# Microcontroller_Memory.net
KiCad netlist of a schematic drawn in Altium Designer
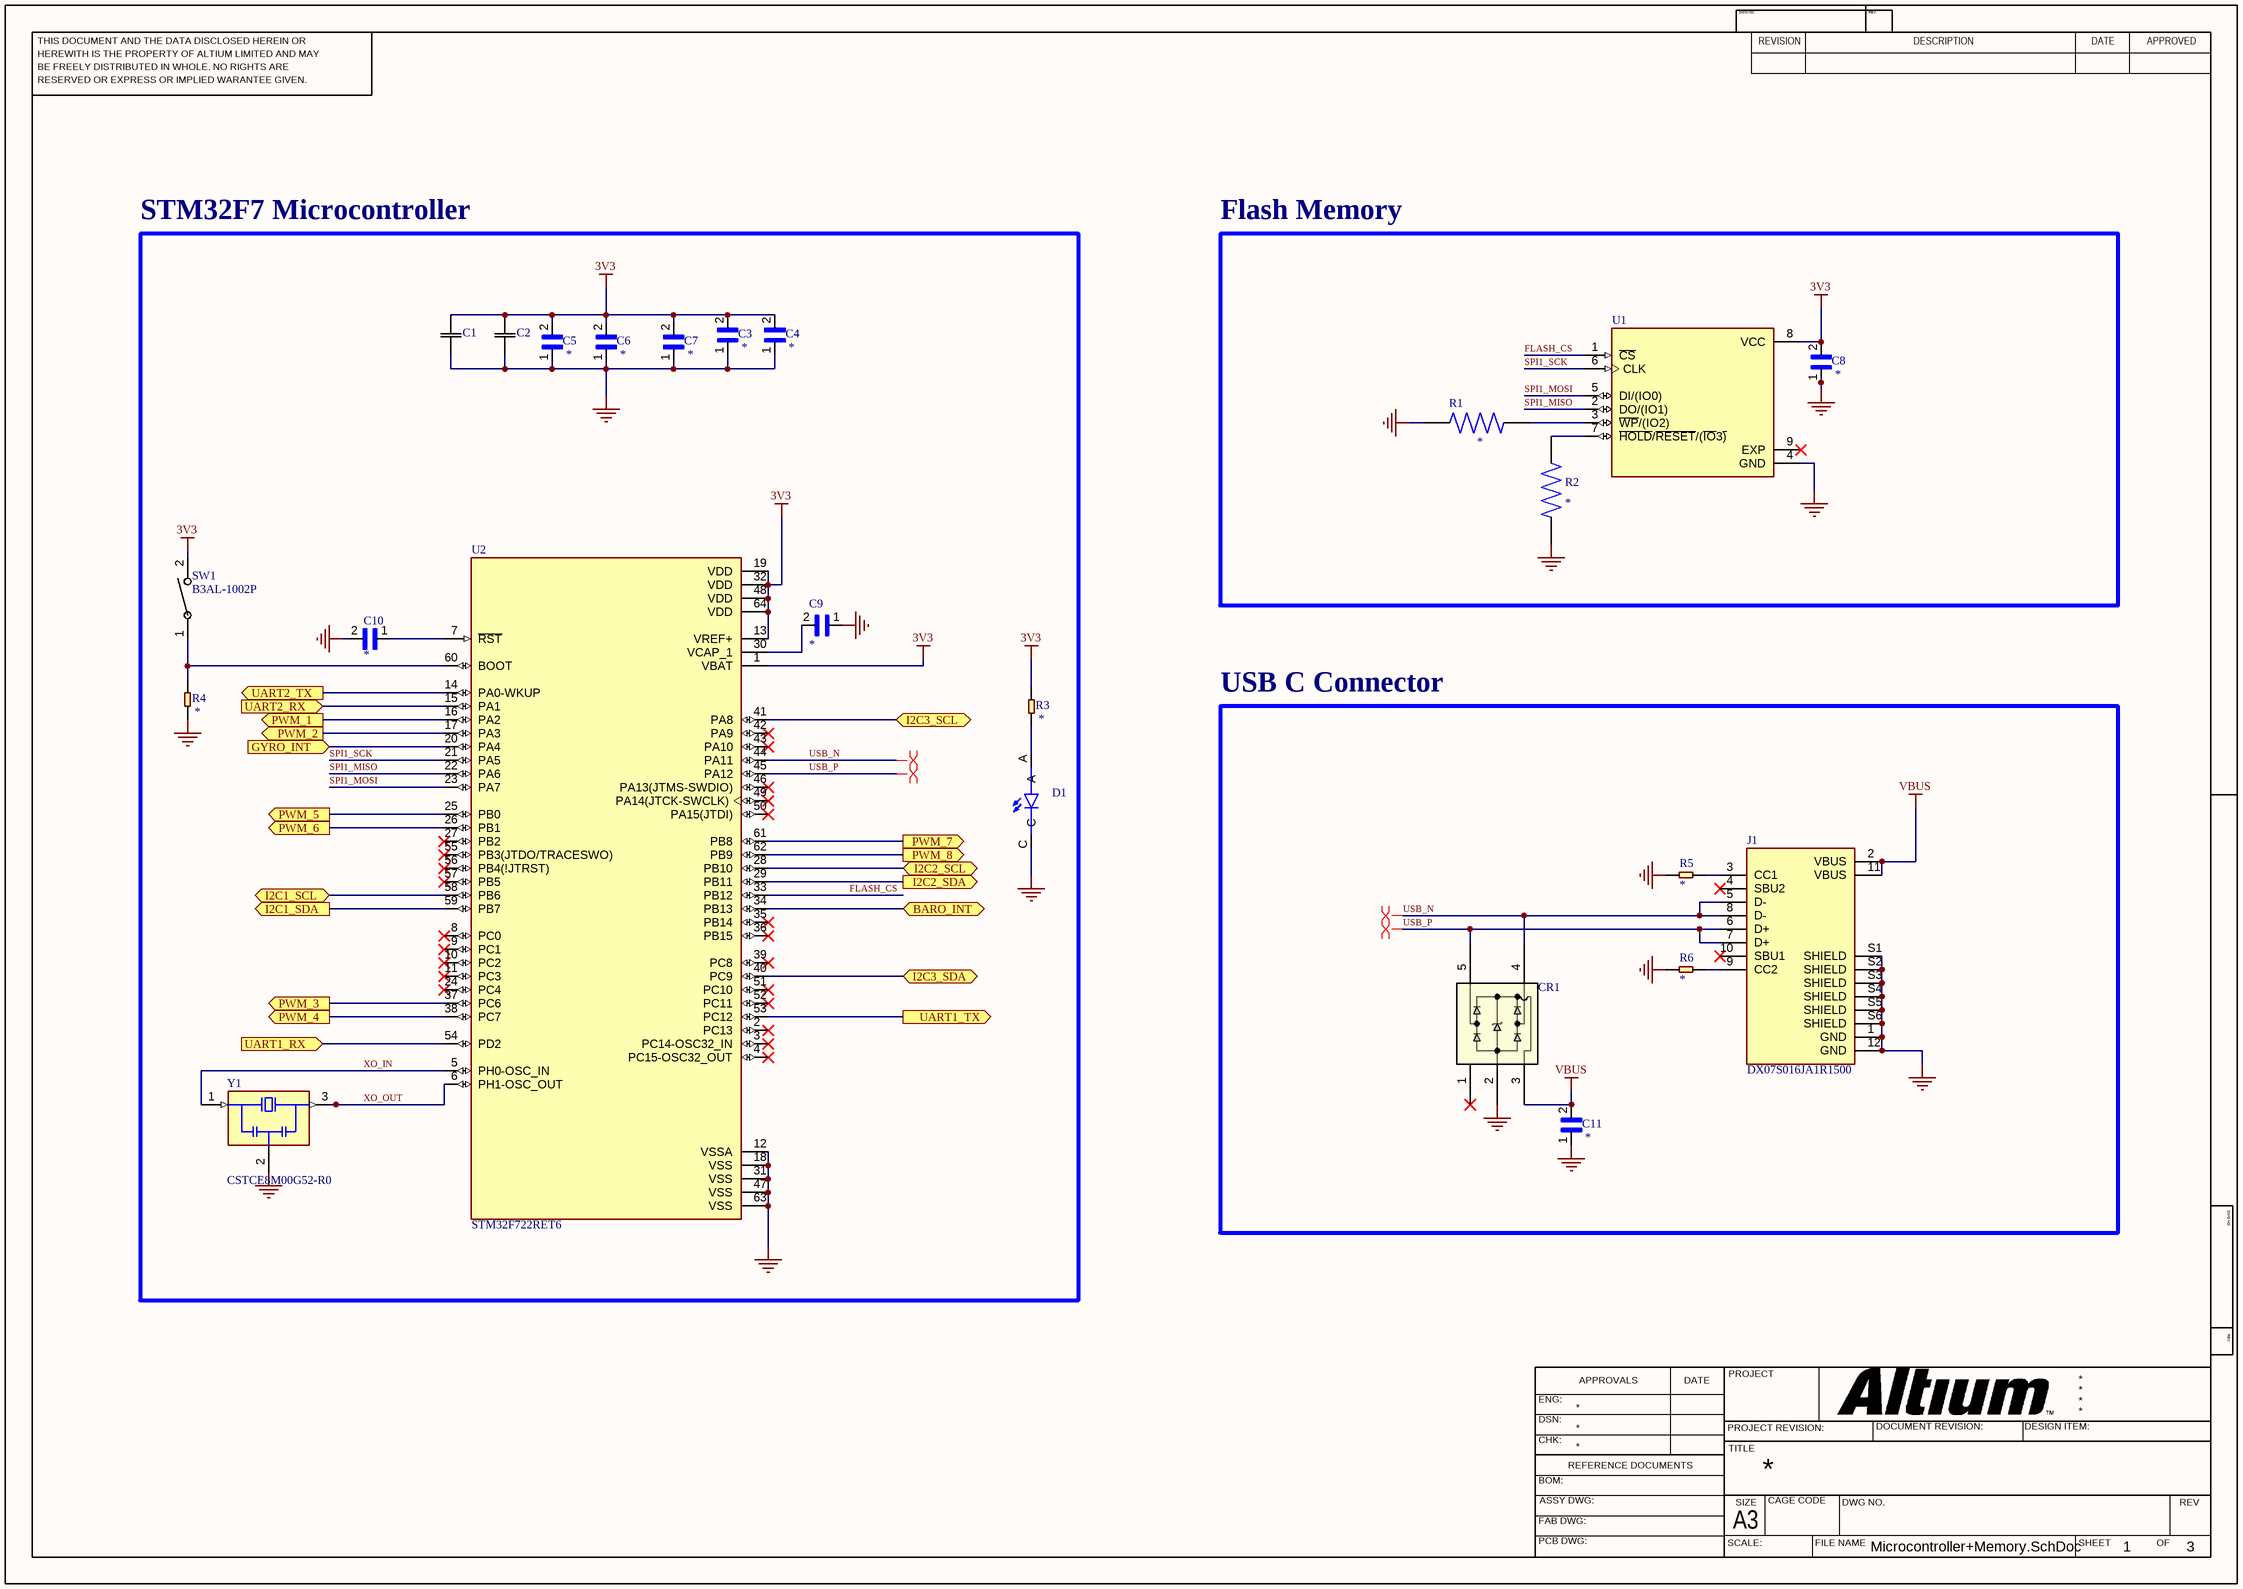
[diagram p0: Microcontroller+Memory.SchDoc]

(export (version "E")
  (design (tool "Eeschema 10.0.6"))
  (components
    (comp (ref "C1")
      (value "CC0402MRX5R6BB106")
      (footprint "CAP_CC0402_YAG")
      (description "No Description Available")
      (libsource (lib "CC0402MRX5R6BB106") (part "CC0402MRX5R6BB106"))
    )
    (comp (ref "C2")
      (value "CC0201MRX5R6BB105")
      (footprint "CAP_CC0201_YAG")
      (description "No Description Available")
      (libsource (lib "CC0201MRX5R6BB105") (part "CC0201MRX5R6BB105"))
    )
    (comp (ref "C3")
      (value "GRM033R61A104KE15D")
      (footprint "CAPC0603X33N")
      (description "SMD capacitor X5R(EIA) with capacitance 0.10uF Tol.10%. Rated voltage 10Vdc 85C")
      (fields (field (name "MF") "Murata Electronics") (field (name "ALTIUM_VALUE") "*"))
      (libsource (lib "GRM033R61A104KE15D") (part "GRM033R61A104KE15D"))
    )
    (comp (ref "C4")
      (value "GRM033R61A104KE15D")
      (footprint "CAPC0603X33N")
      (description "SMD capacitor X5R(EIA) with capacitance 0.10uF Tol.10%. Rated voltage 10Vdc 85C")
      (fields (field (name "MF") "Murata Electronics") (field (name "ALTIUM_VALUE") "*"))
      (libsource (lib "GRM033R61A104KE15D") (part "GRM033R61A104KE15D"))
    )
    (comp (ref "C5")
      (value "GRM033R61A104KE15D")
      (footprint "CAPC0603X33N")
      (description "SMD capacitor X5R(EIA) with capacitance 0.10uF Tol.10%. Rated voltage 10Vdc 85C")
      (fields (field (name "MF") "Murata Electronics") (field (name "ALTIUM_VALUE") "*"))
      (libsource (lib "GRM033R61A104KE15D") (part "GRM033R61A104KE15D"))
    )
    (comp (ref "C6")
      (value "GRM033R61A104KE15D")
      (footprint "CAPC0603X33N")
      (description "SMD capacitor X5R(EIA) with capacitance 0.10uF Tol.10%. Rated voltage 10Vdc 85C")
      (fields (field (name "MF") "Murata Electronics") (field (name "ALTIUM_VALUE") "*"))
      (libsource (lib "GRM033R61A104KE15D") (part "GRM033R61A104KE15D"))
    )
    (comp (ref "C7")
      (value "GRM033R61A104KE15D")
      (footprint "CAPC0603X33N")
      (description "SMD capacitor X5R(EIA) with capacitance 0.10uF Tol.10%. Rated voltage 10Vdc 85C")
      (fields (field (name "MF") "Murata Electronics") (field (name "ALTIUM_VALUE") "*"))
      (libsource (lib "GRM033R61A104KE15D") (part "GRM033R61A104KE15D"))
    )
    (comp (ref "C8")
      (value "GRM033R61A104KE15D")
      (footprint "CAPC0603X33N")
      (description "SMD capacitor X5R(EIA) with capacitance 0.10uF Tol.10%. Rated voltage 10Vdc 85C")
      (fields (field (name "MF") "Murata Electronics") (field (name "ALTIUM_VALUE") "*"))
      (libsource (lib "GRM033R61A104KE15D") (part "GRM033R61A104KE15D"))
    )
    (comp (ref "C9")
      (value "CC0402MRX5R6BB475")
      (footprint "CAPC1005X55N")
      (description "0402 4700000 pF 10 V Â±20 % Tol. X5R Surface Mount Multilayer Ceramic Capacitor")
      (fields (field (name "ALTIUM_VALUE") "*"))
      (libsource (lib "CC0402MRX5R6BB475") (part "CC0402MRX5R6BB475"))
    )
    (comp (ref "C10")
      (value "GRM033R61A104KE15D")
      (footprint "CAPC0603X33N")
      (description "SMD capacitor X5R(EIA) with capacitance 0.10uF Tol.10%. Rated voltage 10Vdc 85C")
      (fields (field (name "MF") "Murata Electronics") (field (name "ALTIUM_VALUE") "*"))
      (libsource (lib "") (part "GRM033R61A104KE15D_1"))
    )
    (comp (ref "C11")
      (value "GRM033R61A104KE15D")
      (footprint "CAPC0603X33N")
      (description "SMD capacitor X5R(EIA) with capacitance 0.10uF Tol.10%. Rated voltage 10Vdc 85C")
      (fields (field (name "MF") "Murata Electronics") (field (name "ALTIUM_VALUE") "*"))
      (libsource (lib "GRM033R61A104KE15D") (part "GRM033R61A104KE15D"))
    )
    (comp (ref "CR1")
      (value "SP3003-02XTG")
      (footprint "SP3003-02XTG:SOT553_LTF")
      (description "No Description Available")
      (libsource (lib "SP3003-02XTG") (part "SP3003-02XTG"))
    )
    (comp (ref "D1")
      (value "LTST-C190KFKT")
      (footprint "LEDM1608X80")
      (description "LED Uni-Color Orange 611nm 2-Pin Chip LED T/R")
      (fields (field (name "MF") "Lite-On Electronics"))
      (libsource (lib "LTST-C190KFKT") (part "LTST-C190KFKT"))
    )
    (comp (ref "J1")
      (value "DX07S016JA1R1500")
      (footprint "JAE_DX07S016JA1R1500")
      (libsource (lib "DX07S016JA1R1500") (part "DX07S016JA1R1500"))
    )
    (comp (ref "R1")
      (value "ERA2AEB512X")
      (footprint "RES_ERA2AEB512X")
      (fields (field (name "ALTIUM_VALUE") "*"))
      (libsource (lib "ERA2AEB512X") (part "ERA2AEB512X"))
    )
    (comp (ref "R2")
      (value "ERA2AEB512X")
      (footprint "RES_ERA2AEB512X")
      (fields (field (name "ALTIUM_VALUE") "*"))
      (libsource (lib "ERA2AEB512X") (part "ERA2AEB512X"))
    )
    (comp (ref "R3")
      (value "SMD-RES-1K-5%-1/16W(0402)")
      (footprint "R0402")
      (description "1 kOhms Â±5% 0.063W, 1/16W Chip Resistor 0402 (1005 Metric) Moisture Resistant Thick Film")
      (fields
        (field (name "ALTIUM_VALUE") "*")
        (field (name "MP") "RC0402JR-071KL")
        (field (name "DIGI-KEY_PART_NUMBER") "311-1.0KJRTR-ND")
      )
      (libsource (lib "") (part "SMD-RES-1K-5%-1/16W(0402)_1"))
    )
    (comp (ref "R4")
      (value "SMD-RES-1K-5%-1/16W(0402)")
      (footprint "R0402")
      (description "1 kOhms Â±5% 0.063W, 1/16W Chip Resistor 0402 (1005 Metric) Moisture Resistant Thick Film")
      (fields
        (field (name "ALTIUM_VALUE") "*")
        (field (name "MP") "RC0402JR-071KL")
        (field (name "DIGI-KEY_PART_NUMBER") "311-1.0KJRTR-ND")
      )
      (libsource (lib "") (part "SMD-RES-1K-5%-1/16W(0402)_1"))
    )
    (comp (ref "R5")
      (value "SMD-RES-1K-5%-1/16W(0402)")
      (footprint "R0402")
      (description "1 kOhms Â±5% 0.063W, 1/16W Chip Resistor 0402 (1005 Metric) Moisture Resistant Thick Film")
      (fields
        (field (name "ALTIUM_VALUE") "*")
        (field (name "MP") "RC0402JR-071KL")
        (field (name "DIGI-KEY_PART_NUMBER") "311-1.0KJRTR-ND")
      )
      (libsource (lib "SMD-RES-1K-5_-1_16W_0402_") (part "SMD-RES-1K-5%-1/16W(0402)"))
    )
    (comp (ref "R6")
      (value "SMD-RES-1K-5%-1/16W(0402)")
      (footprint "R0402")
      (description "1 kOhms Â±5% 0.063W, 1/16W Chip Resistor 0402 (1005 Metric) Moisture Resistant Thick Film")
      (fields
        (field (name "ALTIUM_VALUE") "*")
        (field (name "MP") "RC0402JR-071KL")
        (field (name "DIGI-KEY_PART_NUMBER") "311-1.0KJRTR-ND")
      )
      (libsource (lib "SMD-RES-1K-5_-1_16W_0402_") (part "SMD-RES-1K-5%-1/16W(0402)"))
    )
    (comp (ref "SW1")
      (value "B3AL-1002P")
      (footprint "B3AL-1002P:SW_3AL-1002P_OMR")
      (description "No Description Available")
      (libsource (lib "B3AL-1002P") (part "B3AL-1002P"))
    )
    (comp (ref "U1")
      (value "W25Q256JVEIQ_TR")
      (footprint "SON127P600X800X80-9N")
      (description "FLASH - NOR Memory IC 256Mb (32M x 8) SPI - Quad I/O 133 MHz 8-WSON (8x6)")
      (fields (field (name "MP") "W25Q256JVEIQ TR") (field (name "MF") "Winbond"))
      (libsource (lib "W25Q256JVEIQ_TR") (part "W25Q256JVEIQ_TR"))
    )
    (comp (ref "U2")
      (value "STM32F722RET6")
      (footprint "QFP50P1200X1200X160-64N")
      (description "ARMÂ® CortexÂ®-M7 STM32F7 Microcontroller IC 32-Bit 216MHz 512KB _512K x 8_ FLASH 64-LQFP _10x10_")
      (fields (field (name "MF") "STMicroelectronics"))
      (libsource (lib "STM32F722RET6") (part "STM32F722RET6"))
    )
    (comp (ref "Y1")
      (value "CSTCE8M00G52-R0")
      (footprint "OSC_CSTCE8M00G52-R0")
      (description "8MHz Ceramic Resonator Built in Capacitor 10pF Â±0.2% -20Â°C ~ 80Â°C Surface Mount")
      (fields (field (name "MF") "Murata"))
      (libsource (lib "CSTCE8M00G52-R0") (part "CSTCE8M00G52-R0"))
    )
  )
  (nets
    (net (code "1") (name "/BARO_INT") (class "Default")
      (node (ref "U2") (pin "34") (pinfunction "PB13_34") (pintype "bidirectional"))
    )
    (net (code "2") (name "/FLASH_CS") (class "Default")
      (node (ref "U1") (pin "1") (pinfunction "~{CS}_1") (pintype "input"))
      (node (ref "U2") (pin "33") (pinfunction "PB12_33") (pintype "bidirectional"))
    )
    (net (code "3") (name "/GYRO_INT") (class "Default")
      (node (ref "U2") (pin "20") (pinfunction "PA4_20") (pintype "bidirectional"))
    )
    (net (code "4") (name "/I2C1_SCL") (class "Default")
      (node (ref "U2") (pin "58") (pinfunction "PB6_58") (pintype "bidirectional"))
    )
    (net (code "5") (name "/I2C1_SDA") (class "Default")
      (node (ref "U2") (pin "59") (pinfunction "PB7_59") (pintype "bidirectional"))
    )
    (net (code "6") (name "/I2C2_SCL") (class "Default")
      (node (ref "U2") (pin "28") (pinfunction "PB10_28") (pintype "bidirectional"))
    )
    (net (code "7") (name "/I2C2_SDA") (class "Default")
      (node (ref "U2") (pin "29") (pinfunction "PB11_29") (pintype "bidirectional"))
    )
    (net (code "8") (name "/I2C3_SCL") (class "Default")
      (node (ref "U2") (pin "41") (pinfunction "PA8_41") (pintype "bidirectional"))
    )
    (net (code "9") (name "/I2C3_SDA") (class "Default")
      (node (ref "U2") (pin "40") (pinfunction "PC9_40") (pintype "bidirectional"))
    )
    (net (code "10") (name "/PWM_1") (class "Default")
      (node (ref "U2") (pin "16") (pinfunction "PA2_16") (pintype "bidirectional"))
    )
    (net (code "11") (name "/PWM_2") (class "Default")
      (node (ref "U2") (pin "17") (pinfunction "PA3_17") (pintype "bidirectional"))
    )
    (net (code "12") (name "/PWM_3") (class "Default")
      (node (ref "U2") (pin "37") (pinfunction "PC6_37") (pintype "bidirectional"))
    )
    (net (code "13") (name "/PWM_4") (class "Default")
      (node (ref "U2") (pin "38") (pinfunction "PC7_38") (pintype "bidirectional"))
    )
    (net (code "14") (name "/PWM_5") (class "Default")
      (node (ref "U2") (pin "25") (pinfunction "PB0_25") (pintype "bidirectional"))
    )
    (net (code "15") (name "/PWM_6") (class "Default")
      (node (ref "U2") (pin "26") (pinfunction "PB1_26") (pintype "bidirectional"))
    )
    (net (code "16") (name "/PWM_7") (class "Default")
      (node (ref "U2") (pin "61") (pinfunction "PB8_61") (pintype "bidirectional"))
    )
    (net (code "17") (name "/PWM_8") (class "Default")
      (node (ref "U2") (pin "62") (pinfunction "PB9_62") (pintype "bidirectional"))
    )
    (net (code "18") (name "/SPI1_MISO") (class "Default")
      (node (ref "U1") (pin "2") (pinfunction "DO/(IO1)_2") (pintype "bidirectional"))
      (node (ref "U2") (pin "22") (pinfunction "PA6_22") (pintype "bidirectional"))
    )
    (net (code "19") (name "/SPI1_MOSI") (class "Default")
      (node (ref "U1") (pin "5") (pinfunction "DI/(IO0)_5") (pintype "bidirectional"))
      (node (ref "U2") (pin "23") (pinfunction "PA7_23") (pintype "bidirectional"))
    )
    (net (code "20") (name "/SPI1_SCK") (class "Default")
      (node (ref "U1") (pin "6") (pinfunction "CLK_6") (pintype "input"))
      (node (ref "U2") (pin "21") (pinfunction "PA5_21") (pintype "bidirectional"))
    )
    (net (code "21") (name "/UART1_RX") (class "Default")
      (node (ref "U2") (pin "54") (pinfunction "PD2_54") (pintype "bidirectional"))
    )
    (net (code "22") (name "/UART1_TX") (class "Default")
      (node (ref "U2") (pin "53") (pinfunction "PC12_53") (pintype "bidirectional"))
    )
    (net (code "23") (name "/UART2_RX") (class "Default")
      (node (ref "U2") (pin "15") (pinfunction "PA1_15") (pintype "bidirectional"))
    )
    (net (code "24") (name "/UART2_TX") (class "Default")
      (node (ref "U2") (pin "14") (pinfunction "PA0-WKUP_14") (pintype "bidirectional"))
    )
    (net (code "25") (name "/USB_N") (class "Default")
      (node (ref "CR1") (pin "4") (pinfunction "4_4") (pintype "passive"))
      (node (ref "J1") (pin "5") (pinfunction "D-_5") (pintype "passive"))
      (node (ref "J1") (pin "8") (pinfunction "D-_8") (pintype "passive"))
      (node (ref "U2") (pin "44") (pinfunction "PA11_44") (pintype "bidirectional"))
    )
    (net (code "26") (name "/USB_P") (class "Default")
      (node (ref "CR1") (pin "5") (pinfunction "5_5") (pintype "passive"))
      (node (ref "J1") (pin "6") (pinfunction "D+_6") (pintype "passive"))
      (node (ref "J1") (pin "7") (pinfunction "D+_7") (pintype "passive"))
      (node (ref "U2") (pin "45") (pinfunction "PA12_45") (pintype "bidirectional"))
    )
    (net (code "27") (name "/XO_IN") (class "Default")
      (node (ref "U2") (pin "5") (pinfunction "PH0-OSC_IN_5") (pintype "bidirectional"))
      (node (ref "Y1") (pin "1") (pinfunction "IN_1") (pintype "input"))
    )
    (net (code "28") (name "/XO_OUT") (class "Default")
      (node (ref "U2") (pin "6") (pinfunction "PH1-OSC_OUT_6") (pintype "bidirectional"))
      (node (ref "Y1") (pin "3") (pinfunction "OUT_3") (pintype "output"))
    )
    (net (code "29") (name "3V3") (class "Default")
      (node (ref "C1") (pin "2") (pinfunction "2_2") (pintype "passive"))
      (node (ref "C2") (pin "2") (pinfunction "2_2") (pintype "passive"))
      (node (ref "C3") (pin "2") (pinfunction "2_2") (pintype "passive"))
      (node (ref "C4") (pin "2") (pinfunction "2_2") (pintype "passive"))
      (node (ref "C5") (pin "2") (pinfunction "2_2") (pintype "passive"))
      (node (ref "C6") (pin "2") (pinfunction "2_2") (pintype "passive"))
      (node (ref "C7") (pin "2") (pinfunction "2_2") (pintype "passive"))
      (node (ref "C8") (pin "2") (pinfunction "2_2") (pintype "passive"))
      (node (ref "R3") (pin "2") (pinfunction "2_2") (pintype "passive"))
      (node (ref "SW1") (pin "2") (pinfunction "2_2") (pintype "passive"))
      (node (ref "U1") (pin "8") (pinfunction "VCC_8") (pintype "power_in"))
      (node (ref "U2") (pin "1") (pinfunction "VBAT_1") (pintype "power_in"))
      (node (ref "U2") (pin "13") (pinfunction "VREF+_13") (pintype "power_in"))
      (node (ref "U2") (pin "19") (pinfunction "VDD_19") (pintype "power_in"))
      (node (ref "U2") (pin "32") (pinfunction "VDD_32") (pintype "power_in"))
      (node (ref "U2") (pin "48") (pinfunction "VDD_48") (pintype "power_in"))
      (node (ref "U2") (pin "64") (pinfunction "VDD_64") (pintype "power_in"))
    )
    (net (code "30") (name "GND") (class "Default")
      (node (ref "C1") (pin "1") (pinfunction "1_1") (pintype "passive"))
      (node (ref "C10") (pin "2") (pinfunction "2_2") (pintype "passive"))
      (node (ref "C11") (pin "1") (pinfunction "1_1") (pintype "passive"))
      (node (ref "C2") (pin "1") (pinfunction "1_1") (pintype "passive"))
      (node (ref "C3") (pin "1") (pinfunction "1_1") (pintype "passive"))
      (node (ref "C4") (pin "1") (pinfunction "1_1") (pintype "passive"))
      (node (ref "C5") (pin "1") (pinfunction "1_1") (pintype "passive"))
      (node (ref "C6") (pin "1") (pinfunction "1_1") (pintype "passive"))
      (node (ref "C7") (pin "1") (pinfunction "1_1") (pintype "passive"))
      (node (ref "C8") (pin "1") (pinfunction "1_1") (pintype "passive"))
      (node (ref "C9") (pin "1") (pinfunction "1_1") (pintype "passive"))
      (node (ref "CR1") (pin "2") (pinfunction "2_2") (pintype "passive"))
      (node (ref "D1") (pin "C") (pinfunction "C_C") (pintype "passive"))
      (node (ref "J1") (pin "1") (pinfunction "GND_1") (pintype "power_in"))
      (node (ref "J1") (pin "12") (pinfunction "GND_12") (pintype "power_in"))
      (node (ref "J1") (pin "S1") (pinfunction "SHIELD_S1") (pintype "passive"))
      (node (ref "J1") (pin "S2") (pinfunction "SHIELD_S2") (pintype "passive"))
      (node (ref "J1") (pin "S3") (pinfunction "SHIELD_S3") (pintype "passive"))
      (node (ref "J1") (pin "S4") (pinfunction "SHIELD_S4") (pintype "passive"))
      (node (ref "J1") (pin "S5") (pinfunction "SHIELD_S5") (pintype "passive"))
      (node (ref "J1") (pin "S6") (pinfunction "SHIELD_S6") (pintype "passive"))
      (node (ref "R1") (pin "1") (pinfunction "1_1") (pintype "passive"))
      (node (ref "R2") (pin "1") (pinfunction "1_1") (pintype "passive"))
      (node (ref "R4") (pin "1") (pinfunction "1_1") (pintype "passive"))
      (node (ref "R5") (pin "2") (pinfunction "2_2") (pintype "passive"))
      (node (ref "R6") (pin "2") (pinfunction "2_2") (pintype "passive"))
      (node (ref "U1") (pin "4") (pinfunction "GND_4") (pintype "power_in"))
      (node (ref "U2") (pin "12") (pinfunction "VSSA_12") (pintype "power_in"))
      (node (ref "U2") (pin "18") (pinfunction "VSS_18") (pintype "power_in"))
      (node (ref "U2") (pin "31") (pinfunction "VSS_31") (pintype "power_in"))
      (node (ref "U2") (pin "47") (pinfunction "VSS_47") (pintype "power_in"))
      (node (ref "U2") (pin "63") (pinfunction "VSS_63") (pintype "power_in"))
      (node (ref "Y1") (pin "2") (pinfunction "GND_2") (pintype "power_in"))
    )
    (net (code "31") (name "Net-(D1-PadA)") (class "Default")
      (node (ref "D1") (pin "A") (pinfunction "A_A") (pintype "passive"))
      (node (ref "R3") (pin "1") (pinfunction "1_1") (pintype "passive"))
    )
    (net (code "32") (name "Net-(J1-CC1)") (class "Default")
      (node (ref "J1") (pin "3") (pinfunction "CC1_3") (pintype "passive"))
      (node (ref "R5") (pin "1") (pinfunction "1_1") (pintype "passive"))
    )
    (net (code "33") (name "Net-(J1-CC2)") (class "Default")
      (node (ref "J1") (pin "9") (pinfunction "CC2_9") (pintype "passive"))
      (node (ref "R6") (pin "1") (pinfunction "1_1") (pintype "passive"))
    )
    (net (code "34") (name "Net-(U1-~{HOLD}{slash}~{RESET}{slash}(~{IO}3~{)})") (class "Default")
      (node (ref "R2") (pin "2") (pinfunction "2_2") (pintype "passive"))
      (node (ref "U1") (pin "7") (pinfunction "~{HOLD}/~{RESET}/(~{IO}3~{)}_7") (pintype "bidirectional"))
    )
    (net (code "35") (name "Net-(U1-~{WP}{slash}(IO2))") (class "Default")
      (node (ref "R1") (pin "2") (pinfunction "2_2") (pintype "passive"))
      (node (ref "U1") (pin "3") (pinfunction "~{WP}/(IO2)_3") (pintype "bidirectional"))
    )
    (net (code "36") (name "Net-(U2-BOOT)") (class "Default")
      (node (ref "R4") (pin "2") (pinfunction "2_2") (pintype "passive"))
      (node (ref "SW1") (pin "1") (pinfunction "1_1") (pintype "passive"))
      (node (ref "U2") (pin "60") (pinfunction "BOOT_60") (pintype "bidirectional"))
    )
    (net (code "37") (name "Net-(U2-VCAP_1)") (class "Default")
      (node (ref "C9") (pin "2") (pinfunction "2_2") (pintype "passive"))
      (node (ref "U2") (pin "30") (pinfunction "VCAP_1_30") (pintype "power_in"))
    )
    (net (code "38") (name "Net-(U2-~{RST})") (class "Default")
      (node (ref "C10") (pin "1") (pinfunction "1_1") (pintype "passive"))
      (node (ref "U2") (pin "7") (pinfunction "~{RST}_7") (pintype "input"))
    )
    (net (code "39") (name "VBUS") (class "Default")
      (node (ref "C11") (pin "2") (pinfunction "2_2") (pintype "passive"))
      (node (ref "CR1") (pin "3") (pinfunction "3_3") (pintype "passive"))
      (node (ref "J1") (pin "11") (pinfunction "VBUS_11") (pintype "power_in"))
      (node (ref "J1") (pin "2") (pinfunction "VBUS_2") (pintype "power_in"))
    )
    (net (code "40") (name "unconnected-(CR1-Pad1)") (class "Default")
      (node (ref "CR1") (pin "1") (pinfunction "1_1") (pintype "passive+no_connect"))
    )
    (net (code "41") (name "unconnected-(J1-SBU1-Pad10)") (class "Default")
      (node (ref "J1") (pin "10") (pinfunction "SBU1_10") (pintype "passive+no_connect"))
    )
    (net (code "42") (name "unconnected-(J1-SBU2-Pad4)") (class "Default")
      (node (ref "J1") (pin "4") (pinfunction "SBU2_4") (pintype "passive+no_connect"))
    )
    (net (code "43") (name "unconnected-(U1-EXP-Pad9)") (class "Default")
      (node (ref "U1") (pin "9") (pinfunction "EXP_9") (pintype "passive+no_connect"))
    )
    (net (code "44") (name "unconnected-(U2-PA9-Pad42)") (class "Default")
      (node (ref "U2") (pin "42") (pinfunction "PA9_42") (pintype "bidirectional+no_connect"))
    )
    (net (code "45") (name "unconnected-(U2-PA10-Pad43)") (class "Default")
      (node (ref "U2") (pin "43") (pinfunction "PA10_43") (pintype "bidirectional+no_connect"))
    )
    (net (code "46") (name "unconnected-(U2-PA13(JTMS-SWDIO)-Pad46)") (class "Default")
      (node (ref "U2") (pin "46") (pinfunction "PA13(JTMS-SWDIO)_46") (pintype "bidirectional+no_connect"))
    )
    (net (code "47") (name "unconnected-(U2-PA14(JTCK-SWCLK)-Pad49)") (class "Default")
      (node (ref "U2") (pin "49") (pinfunction "PA14(JTCK-SWCLK)_49") (pintype "bidirectional+no_connect"))
    )
    (net (code "48") (name "unconnected-(U2-PA15(JTDI)-Pad50)") (class "Default")
      (node (ref "U2") (pin "50") (pinfunction "PA15(JTDI)_50") (pintype "bidirectional+no_connect"))
    )
    (net (code "49") (name "unconnected-(U2-PB2-Pad27)") (class "Default")
      (node (ref "U2") (pin "27") (pinfunction "PB2_27") (pintype "bidirectional+no_connect"))
    )
    (net (code "50") (name "unconnected-(U2-PB3(JTDO{slash}TRACESWO)-Pad55)") (class "Default")
      (node (ref "U2") (pin "55") (pinfunction "PB3(JTDO/TRACESWO)_55") (pintype "bidirectional+no_connect"))
    )
    (net (code "51") (name "unconnected-(U2-PB4(!JTRST)-Pad56)") (class "Default")
      (node (ref "U2") (pin "56") (pinfunction "PB4(!JTRST)_56") (pintype "bidirectional+no_connect"))
    )
    (net (code "52") (name "unconnected-(U2-PB5-Pad57)") (class "Default")
      (node (ref "U2") (pin "57") (pinfunction "PB5_57") (pintype "bidirectional+no_connect"))
    )
    (net (code "53") (name "unconnected-(U2-PB14-Pad35)") (class "Default")
      (node (ref "U2") (pin "35") (pinfunction "PB14_35") (pintype "bidirectional+no_connect"))
    )
    (net (code "54") (name "unconnected-(U2-PB15-Pad36)") (class "Default")
      (node (ref "U2") (pin "36") (pinfunction "PB15_36") (pintype "bidirectional+no_connect"))
    )
    (net (code "55") (name "unconnected-(U2-PC0-Pad8)") (class "Default")
      (node (ref "U2") (pin "8") (pinfunction "PC0_8") (pintype "bidirectional+no_connect"))
    )
    (net (code "56") (name "unconnected-(U2-PC1-Pad9)") (class "Default")
      (node (ref "U2") (pin "9") (pinfunction "PC1_9") (pintype "bidirectional+no_connect"))
    )
    (net (code "57") (name "unconnected-(U2-PC2-Pad10)") (class "Default")
      (node (ref "U2") (pin "10") (pinfunction "PC2_10") (pintype "bidirectional+no_connect"))
    )
    (net (code "58") (name "unconnected-(U2-PC3-Pad11)") (class "Default")
      (node (ref "U2") (pin "11") (pinfunction "PC3_11") (pintype "bidirectional+no_connect"))
    )
    (net (code "59") (name "unconnected-(U2-PC4-Pad24)") (class "Default")
      (node (ref "U2") (pin "24") (pinfunction "PC4_24") (pintype "bidirectional+no_connect"))
    )
    (net (code "60") (name "unconnected-(U2-PC8-Pad39)") (class "Default")
      (node (ref "U2") (pin "39") (pinfunction "PC8_39") (pintype "bidirectional+no_connect"))
    )
    (net (code "61") (name "unconnected-(U2-PC10-Pad51)") (class "Default")
      (node (ref "U2") (pin "51") (pinfunction "PC10_51") (pintype "bidirectional+no_connect"))
    )
    (net (code "62") (name "unconnected-(U2-PC11-Pad52)") (class "Default")
      (node (ref "U2") (pin "52") (pinfunction "PC11_52") (pintype "bidirectional+no_connect"))
    )
    (net (code "63") (name "unconnected-(U2-PC13-Pad2)") (class "Default")
      (node (ref "U2") (pin "2") (pinfunction "PC13_2") (pintype "bidirectional+no_connect"))
    )
    (net (code "64") (name "unconnected-(U2-PC14-OSC32_IN-Pad3)") (class "Default")
      (node (ref "U2") (pin "3") (pinfunction "PC14-OSC32_IN_3") (pintype "bidirectional+no_connect"))
    )
    (net (code "65") (name "unconnected-(U2-PC15-OSC32_OUT-Pad4)") (class "Default")
      (node (ref "U2") (pin "4") (pinfunction "PC15-OSC32_OUT_4") (pintype "bidirectional+no_connect"))
    )
  )
)
